# NG2092_IMX378.net
KiCad netlist of a schematic drawn in Altium Designer
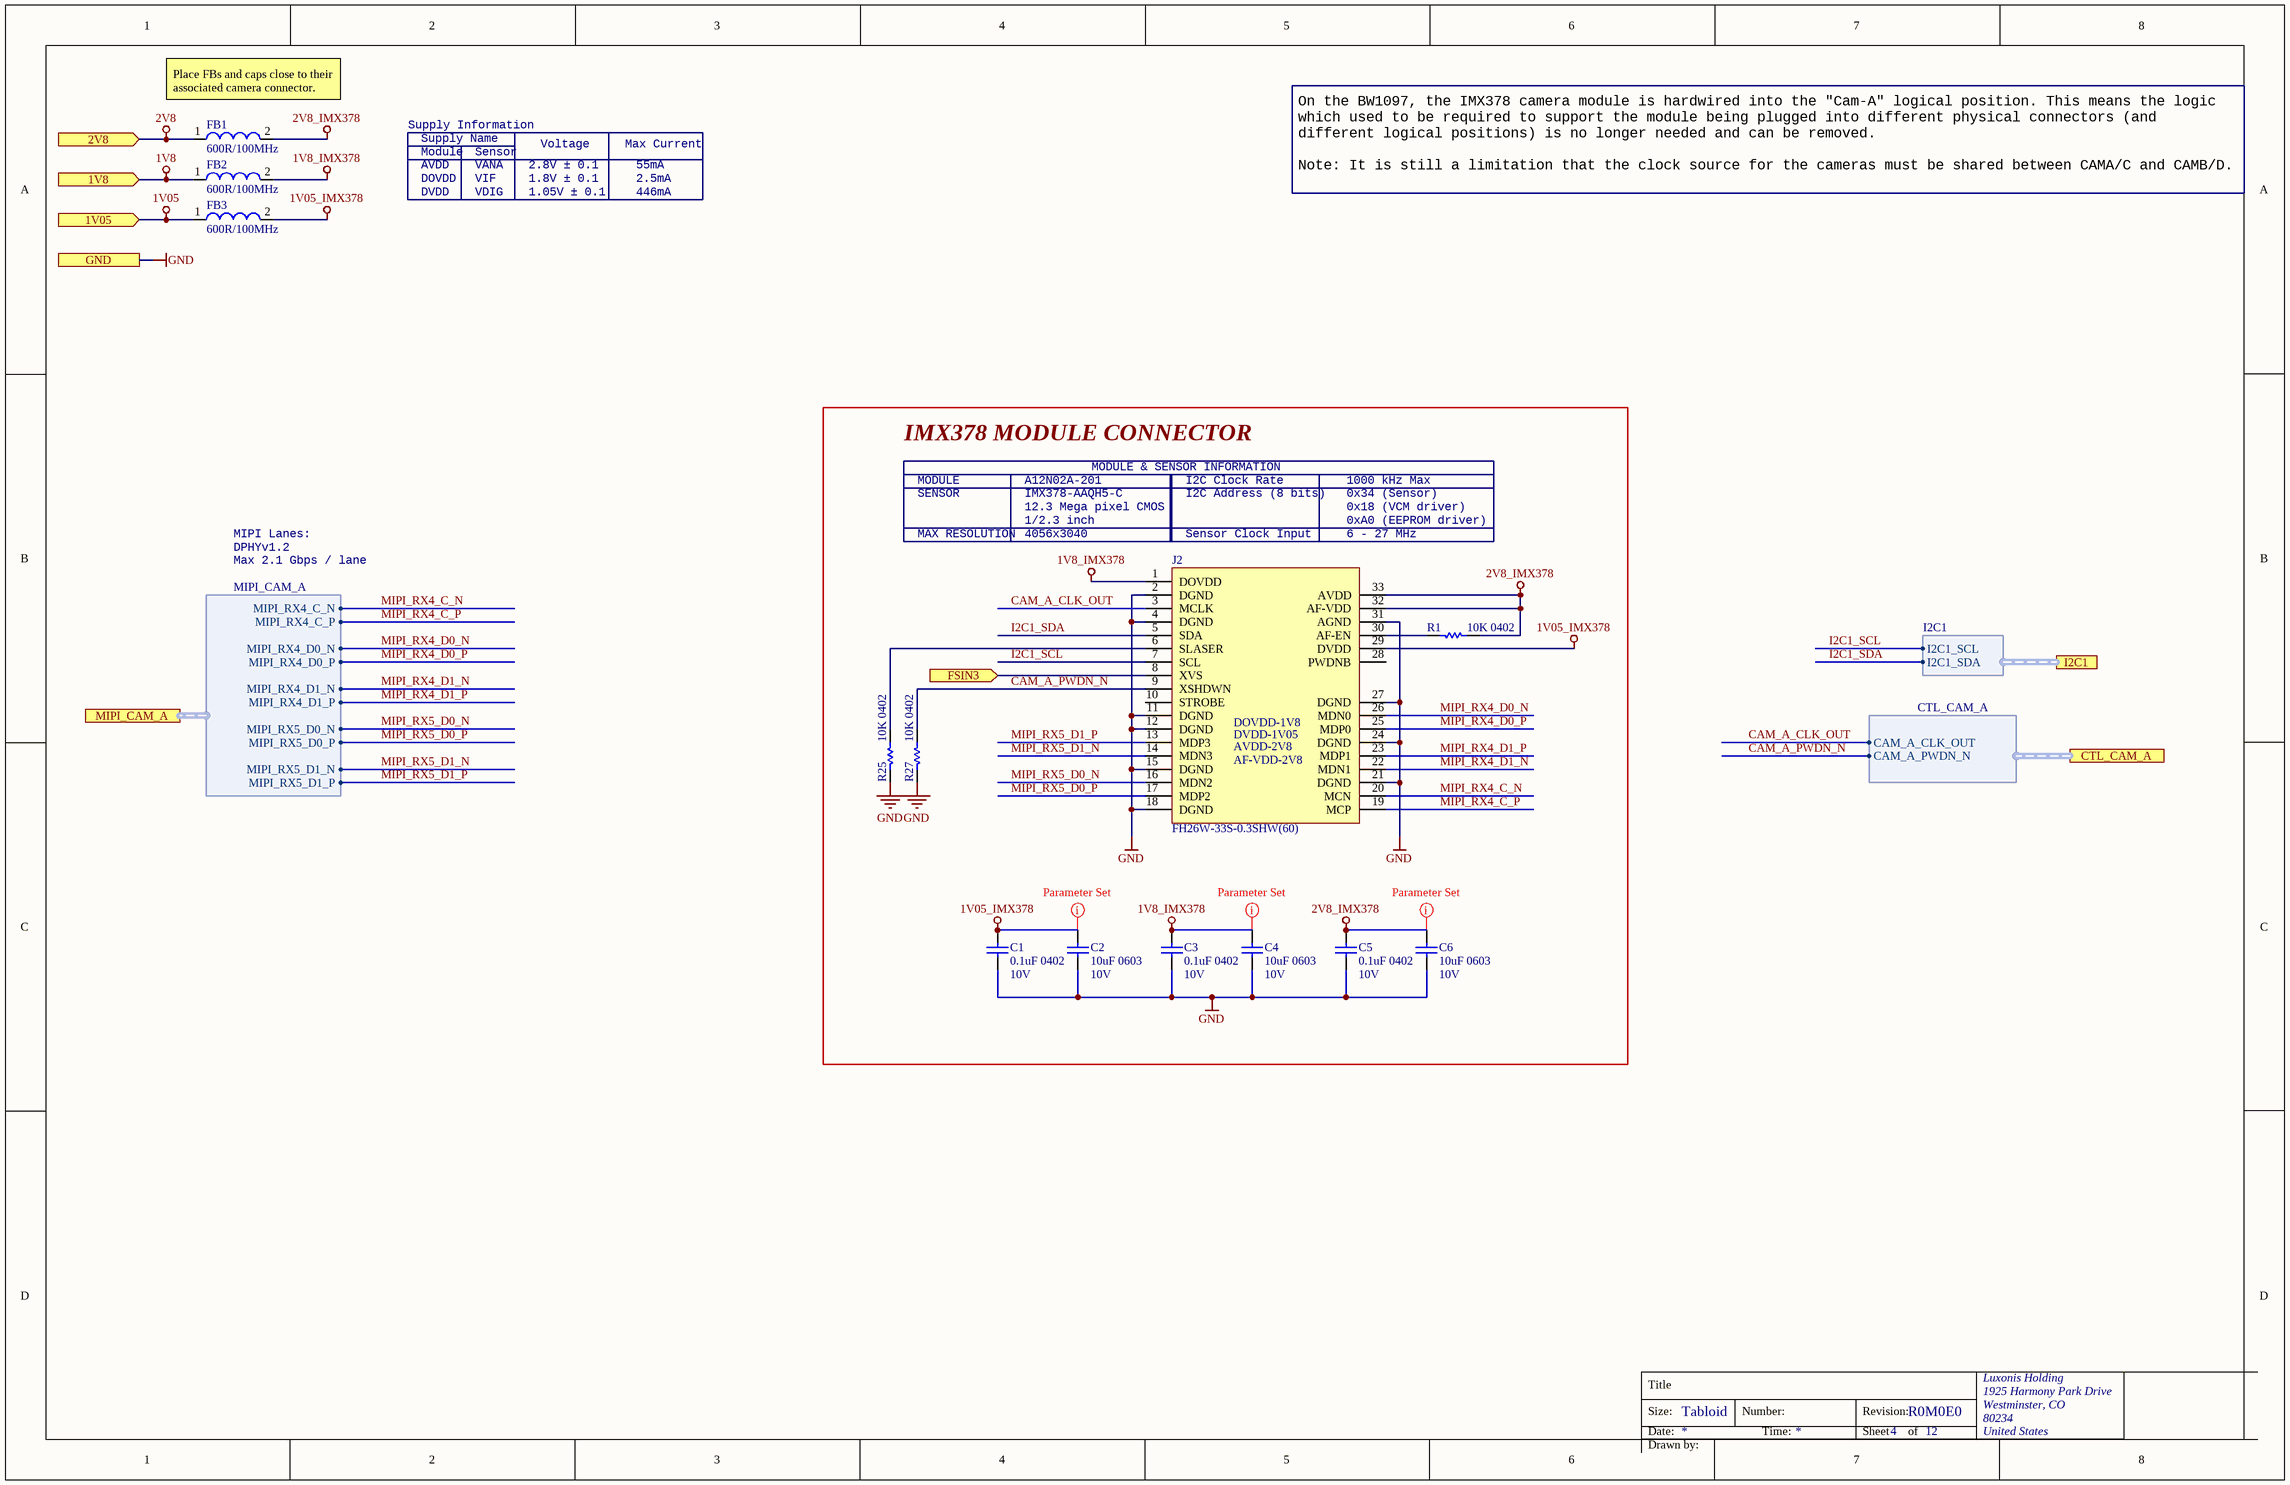
[diagram p0: NG2092_IMX378.SchDoc]

(export (version "E")
  (design (tool "Eeschema 10.0.6"))
  (components
    (comp (ref "C1")
      (value "0.1uF 0402")
      (footprint "CAP_Altium_Vault_Generic:CAPC0402(1005)70_L")
      (description "CAP CER 0.1UF 10V X7R 0402 5%")
      (fields (field (name "TOLERANCE") "5%") (field (name "VOLTAGE RATING") "10V"))
      (libsource (lib "LuxonisMaster") (part "GRM155R71A104JA01D"))
    )
    (comp (ref "C2")
      (value "10uF 0603")
      (footprint "CAP_Altium_Vault_Generic:CAPC0603(1608)100_L")
      (description "CAP CER 10UF 10V X5R 0603 20%")
      (fields (field (name "TOLERANCE") "20%") (field (name "VOLTAGE RATING") "10V"))
      (libsource (lib "LuxonisMaster") (part "GRM188R61A106ME69D"))
    )
    (comp (ref "C3")
      (value "0.1uF 0402")
      (footprint "CAP_Altium_Vault_Generic:CAPC0402(1005)70_L")
      (description "CAP CER 0.1UF 10V X7R 0402 5%")
      (fields (field (name "TOLERANCE") "5%") (field (name "VOLTAGE RATING") "10V"))
      (libsource (lib "LuxonisMaster") (part "GRM155R71A104JA01D"))
    )
    (comp (ref "C4")
      (value "10uF 0603")
      (footprint "CAP_Altium_Vault_Generic:CAPC0603(1608)100_L")
      (description "CAP CER 10UF 10V X5R 0603 20%")
      (fields (field (name "TOLERANCE") "20%") (field (name "VOLTAGE RATING") "10V"))
      (libsource (lib "LuxonisMaster") (part "GRM188R61A106ME69D"))
    )
    (comp (ref "C5")
      (value "0.1uF 0402")
      (footprint "CAP_Altium_Vault_Generic:CAPC0402(1005)70_L")
      (description "CAP CER 0.1UF 10V X7R 0402 5%")
      (fields (field (name "TOLERANCE") "5%") (field (name "VOLTAGE RATING") "10V"))
      (libsource (lib "LuxonisMaster") (part "GRM155R71A104JA01D"))
    )
    (comp (ref "C6")
      (value "10uF 0603")
      (footprint "CAP_Altium_Vault_Generic:CAPC0603(1608)100_L")
      (description "CAP CER 10UF 10V X5R 0603 20%")
      (fields (field (name "TOLERANCE") "20%") (field (name "VOLTAGE RATING") "10V"))
      (libsource (lib "LuxonisMaster") (part "GRM188R61A106ME69D"))
    )
    (comp (ref "FB1")
      (value "600R/100MHz")
      (footprint "LuxonisMaster:2508056017Y2")
      (description "FERRITE BEAD, 0.1OHM, 2A, 0805, 600R/100MHz")
      (fields (field (name "TOLERANCE") "25%"))
      (libsource (lib "LuxonisMaster") (part "2508056017Y2"))
    )
    (comp (ref "FB2")
      (value "600R/100MHz")
      (footprint "LuxonisMaster:2508056017Y2")
      (description "FERRITE BEAD, 0.1OHM, 2A, 0805, 600R/100MHz")
      (fields (field (name "TOLERANCE") "25%"))
      (libsource (lib "LuxonisMaster") (part "2508056017Y2"))
    )
    (comp (ref "FB3")
      (value "600R/100MHz")
      (footprint "LuxonisMaster:2508056017Y2")
      (description "FERRITE BEAD, 0.1OHM, 2A, 0805, 600R/100MHz")
      (fields (field (name "TOLERANCE") "25%"))
      (libsource (lib "LuxonisMaster") (part "2508056017Y2"))
    )
    (comp (ref "J2")
      (value "FH26W-33S-0.3SHW(60)")
      (footprint "AC-PY004-IMX378")
      (description "FFC/FPC Connector, 33 Contact(s), 1 Row(s), Female, Right Angle, Surface Mount Terminal")
      (libsource (lib "NG2092") (part "AC_PY004-IMX378_CON"))
    )
    (comp (ref "R1")
      (value "10K 0402")
      (footprint "RES_Altium_Vault_Generic:RESC0402(1005)_L")
      (fields (field (name "TOLERANCE") "1%"))
      (libsource (lib "LuxonisMaster") (part "RC0402FR-1310KL"))
    )
    (comp (ref "R25")
      (value "10K 0402")
      (footprint "RES_Altium_Vault_Generic:RESC0402(1005)_L")
      (fields (field (name "TOLERANCE") "1%"))
      (libsource (lib "LuxonisMaster") (part "RC0402FR-1310KL"))
    )
    (comp (ref "R27")
      (value "10K 0402")
      (footprint "RES_Altium_Vault_Generic:RESC0402(1005)_L")
      (fields (field (name "TOLERANCE") "1%"))
      (libsource (lib "LuxonisMaster") (part "RC0402FR-1310KL"))
    )
  )
  (nets
    (net (code "4") (name "/CAM_A_CLK_OUT") (class "Default")
      (node (ref "J2") (pin "3") (pinfunction "MCLK_3") (pintype "passive"))
    )
    (net (code "5") (name "/CAM_A_PWDN_N") (class "Default")
      (node (ref "J2") (pin "9") (pinfunction "XSHDWN_9") (pintype "passive"))
      (node (ref "R27") (pin "1") (pinfunction "1_1") (pintype "passive"))
    )
    (net (code "6") (name "/FSIN3") (class "Default")
      (node (ref "J2") (pin "8") (pinfunction "XVS_8") (pintype "passive"))
    )
    (net (code "7") (name "/I2C1_SCL") (class "Default")
      (node (ref "J2") (pin "7") (pinfunction "SCL_7") (pintype "passive"))
    )
    (net (code "8") (name "/I2C1_SDA") (class "Default")
      (node (ref "J2") (pin "5") (pinfunction "SDA_5") (pintype "passive"))
    )
    (net (code "9") (name "/MIPI_RX4_C_N") (class "Default")
      (node (ref "J2") (pin "20") (pinfunction "MCN_20") (pintype "passive"))
    )
    (net (code "10") (name "/MIPI_RX4_C_P") (class "Default")
      (node (ref "J2") (pin "19") (pinfunction "MCP_19") (pintype "passive"))
    )
    (net (code "11") (name "/MIPI_RX4_D0_N") (class "Default")
      (node (ref "J2") (pin "26") (pinfunction "MDN0_26") (pintype "passive"))
    )
    (net (code "12") (name "/MIPI_RX4_D0_P") (class "Default")
      (node (ref "J2") (pin "25") (pinfunction "MDP0_25") (pintype "passive"))
    )
    (net (code "13") (name "/MIPI_RX4_D1_N") (class "Default")
      (node (ref "J2") (pin "22") (pinfunction "MDN1_22") (pintype "passive"))
    )
    (net (code "14") (name "/MIPI_RX4_D1_P") (class "Default")
      (node (ref "J2") (pin "23") (pinfunction "MDP1_23") (pintype "passive"))
    )
    (net (code "15") (name "/MIPI_RX5_D0_N") (class "Default")
      (node (ref "J2") (pin "16") (pinfunction "MDN2_16") (pintype "passive"))
    )
    (net (code "16") (name "/MIPI_RX5_D0_P") (class "Default")
      (node (ref "J2") (pin "17") (pinfunction "MDP2_17") (pintype "passive"))
    )
    (net (code "17") (name "/MIPI_RX5_D1_N") (class "Default")
      (node (ref "J2") (pin "14") (pinfunction "MDN3_14") (pintype "passive"))
    )
    (net (code "18") (name "/MIPI_RX5_D1_P") (class "Default")
      (node (ref "J2") (pin "13") (pinfunction "MDP3_13") (pintype "passive"))
    )
    (net (code "22") (name "1V05") (class "Default")
      (node (ref "FB3") (pin "1") (pinfunction "1_1") (pintype "passive"))
    )
    (net (code "23") (name "1V05_IMX378") (class "Default")
      (node (ref "C1") (pin "2") (pinfunction "2_2") (pintype "passive"))
      (node (ref "C2") (pin "2") (pinfunction "2_2") (pintype "passive"))
      (node (ref "FB3") (pin "2") (pinfunction "2_2") (pintype "passive"))
      (node (ref "J2") (pin "29") (pinfunction "DVDD_29") (pintype "passive"))
    )
    (net (code "24") (name "1V8") (class "Default")
      (node (ref "FB2") (pin "1") (pinfunction "1_1") (pintype "passive"))
    )
    (net (code "25") (name "1V8_IMX378") (class "Default")
      (node (ref "C3") (pin "2") (pinfunction "2_2") (pintype "passive"))
      (node (ref "C4") (pin "2") (pinfunction "2_2") (pintype "passive"))
      (node (ref "FB2") (pin "2") (pinfunction "2_2") (pintype "passive"))
      (node (ref "J2") (pin "1") (pinfunction "DOVDD_1") (pintype "passive"))
    )
    (net (code "26") (name "2V8") (class "Default")
      (node (ref "FB1") (pin "1") (pinfunction "1_1") (pintype "passive"))
    )
    (net (code "27") (name "2V8_IMX378") (class "Default")
      (node (ref "C5") (pin "2") (pinfunction "2_2") (pintype "passive"))
      (node (ref "C6") (pin "2") (pinfunction "2_2") (pintype "passive"))
      (node (ref "FB1") (pin "2") (pinfunction "2_2") (pintype "passive"))
      (node (ref "J2") (pin "32") (pinfunction "AF-VDD_32") (pintype "passive"))
      (node (ref "J2") (pin "33") (pinfunction "AVDD_33") (pintype "passive"))
      (node (ref "R1") (pin "1") (pinfunction "1_1") (pintype "passive"))
    )
    (net (code "28") (name "GND") (class "Default")
      (node (ref "C1") (pin "1") (pinfunction "1_1") (pintype "passive"))
      (node (ref "C2") (pin "1") (pinfunction "1_1") (pintype "passive"))
      (node (ref "C3") (pin "1") (pinfunction "1_1") (pintype "passive"))
      (node (ref "C4") (pin "1") (pinfunction "1_1") (pintype "passive"))
      (node (ref "C5") (pin "1") (pinfunction "1_1") (pintype "passive"))
      (node (ref "C6") (pin "1") (pinfunction "1_1") (pintype "passive"))
      (node (ref "J2") (pin "11") (pinfunction "DGND_11") (pintype "passive"))
      (node (ref "J2") (pin "12") (pinfunction "DGND_12") (pintype "passive"))
      (node (ref "J2") (pin "15") (pinfunction "DGND_15") (pintype "passive"))
      (node (ref "J2") (pin "18") (pinfunction "DGND_18") (pintype "passive"))
      (node (ref "J2") (pin "2") (pinfunction "DGND_2") (pintype "passive"))
      (node (ref "J2") (pin "21") (pinfunction "DGND_21") (pintype "passive"))
      (node (ref "J2") (pin "24") (pinfunction "DGND_24") (pintype "passive"))
      (node (ref "J2") (pin "27") (pinfunction "DGND_27") (pintype "passive"))
      (node (ref "J2") (pin "31") (pinfunction "AGND_31") (pintype "passive"))
      (node (ref "J2") (pin "4") (pinfunction "DGND_4") (pintype "passive"))
      (node (ref "R25") (pin "2") (pinfunction "2_2") (pintype "passive"))
      (node (ref "R27") (pin "2") (pinfunction "2_2") (pintype "passive"))
    )
    (net (code "29") (name "Net-(J2-AF-EN)") (class "Default")
      (node (ref "J2") (pin "30") (pinfunction "AF-EN_30") (pintype "passive"))
      (node (ref "R1") (pin "2") (pinfunction "2_2") (pintype "passive"))
    )
    (net (code "30") (name "Net-(J2-SLASER)") (class "Default")
      (node (ref "J2") (pin "6") (pinfunction "SLASER_6") (pintype "passive"))
      (node (ref "R25") (pin "1") (pinfunction "1_1") (pintype "passive"))
    )
    (net (code "31") (name "unconnected-(J2-PWDNB-Pad28)") (class "Default")
      (node (ref "J2") (pin "28") (pinfunction "PWDNB_28") (pintype "passive"))
    )
    (net (code "32") (name "unconnected-(J2-STROBE-Pad10)") (class "Default")
      (node (ref "J2") (pin "10") (pinfunction "STROBE_10") (pintype "passive"))
    )
  )
)
